# RaspiComm_v3.net
KiCad netlist of a schematic drawn in EAGLE
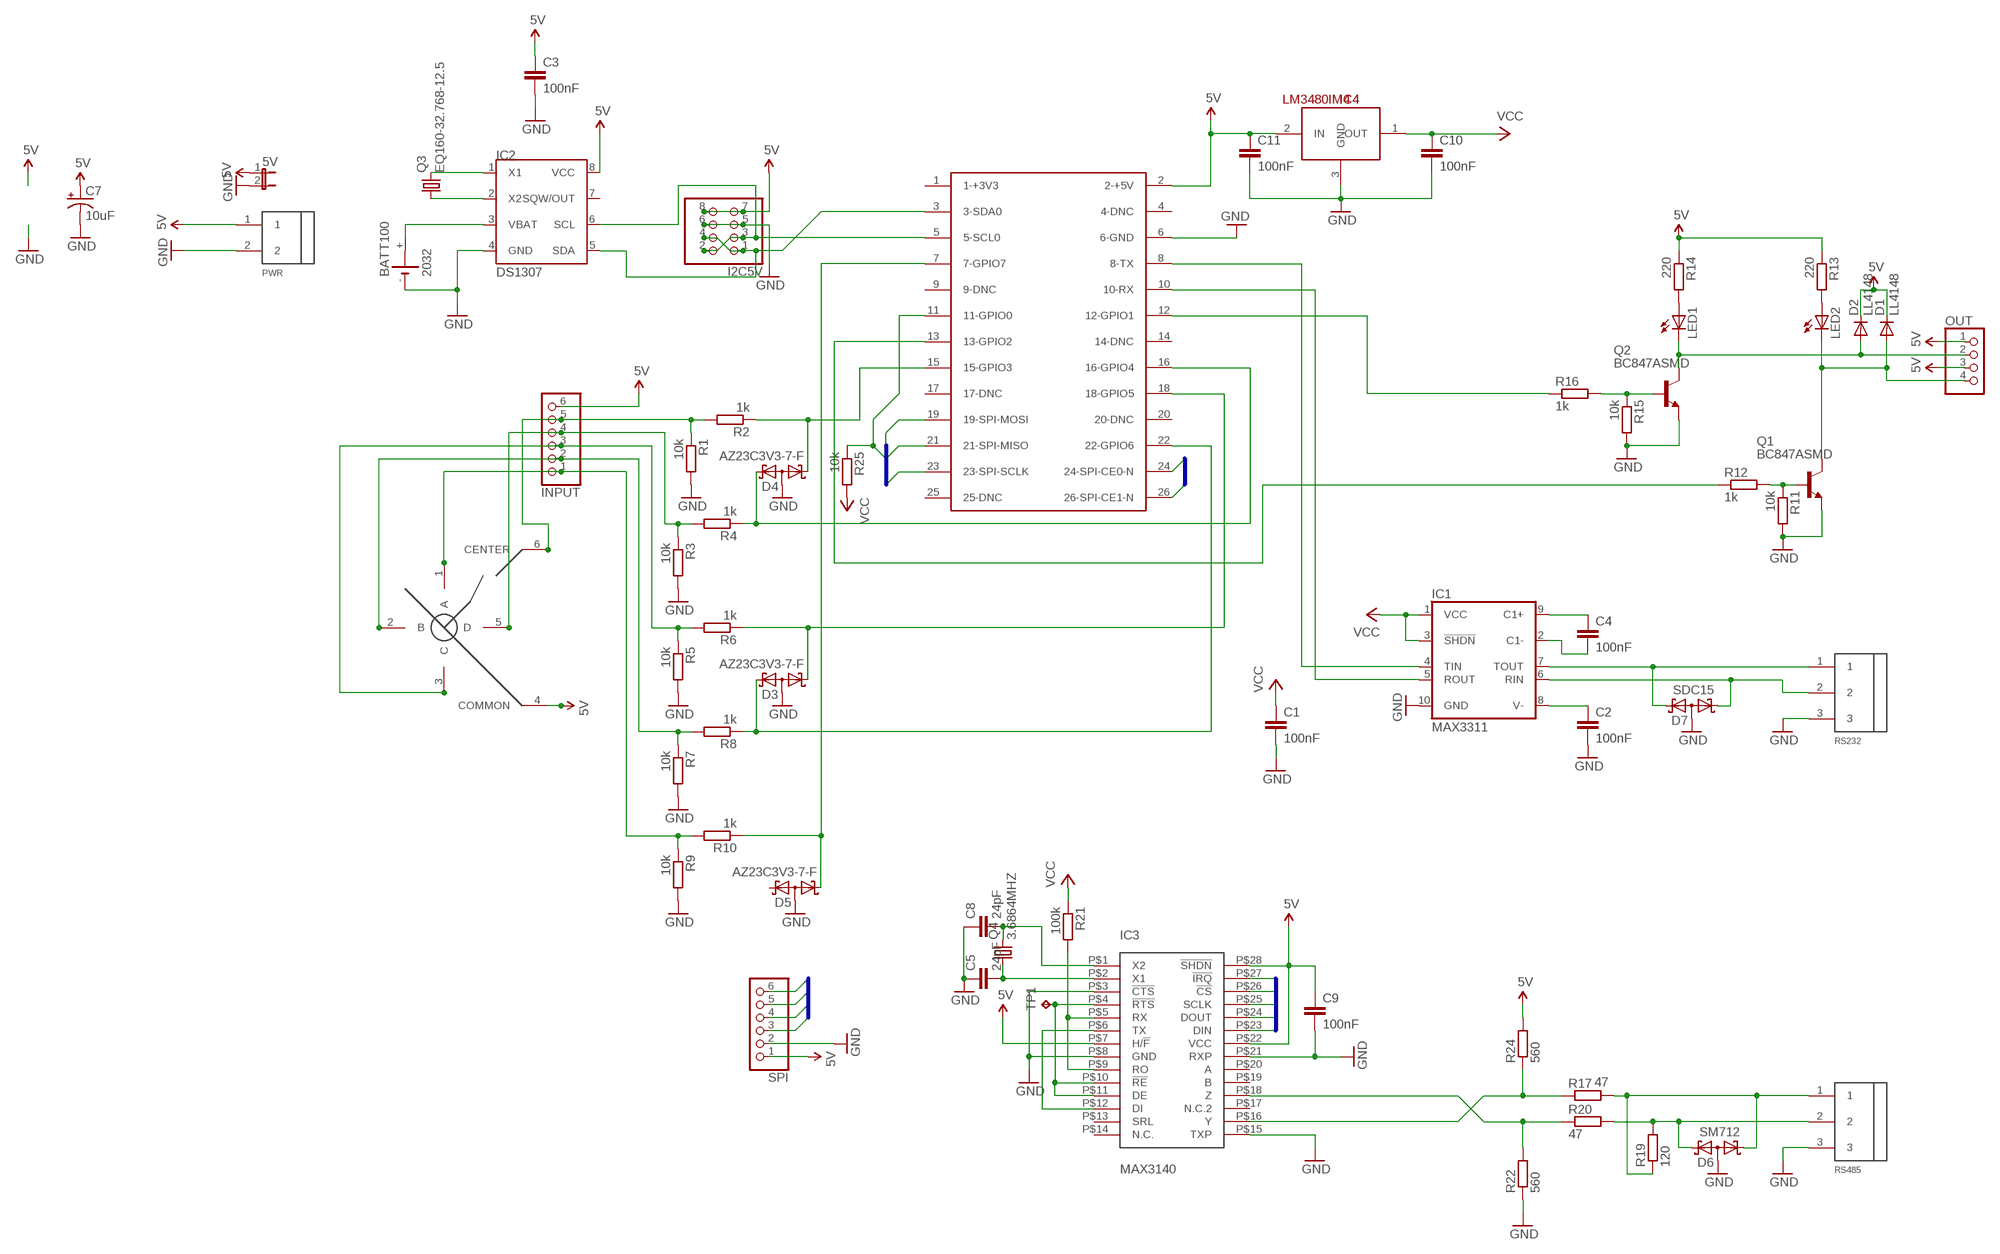
[diagram p0: schematic, sheet 1]

(export (version "E")
  (design (tool "Eeschema 10.0.6"))
  (components
    (comp (ref "5V")
      (value "JP1E")
      (footprint "eagle-import:JP1")
      (libsource (lib "eagle-import") (part "JP1E"))
    )
    (comp (ref "BATT100")
      (value "2032")
      (footprint "eagle-import:KZH20SMD")
      (libsource (lib "eagle-import") (part "2032"))
    )
    (comp (ref "C1")
      (value "100nF")
      (footprint "eagle-import:C0603")
      (libsource (lib "eagle-import") (part "C-EUC0603"))
    )
    (comp (ref "C2")
      (value "100nF")
      (footprint "eagle-import:C0603")
      (libsource (lib "eagle-import") (part "C-EUC0603"))
    )
    (comp (ref "C3")
      (value "100nF")
      (footprint "eagle-import:C0603")
      (libsource (lib "eagle-import") (part "C-EUC0603"))
    )
    (comp (ref "C4")
      (value "100nF")
      (footprint "eagle-import:C0603")
      (libsource (lib "eagle-import") (part "C-EUC0603"))
    )
    (comp (ref "C5")
      (value "24pF")
      (footprint "eagle-import:C0603")
      (libsource (lib "eagle-import") (part "C-EUC0603"))
    )
    (comp (ref "C7")
      (value "10uF")
      (footprint "eagle-import:B(3528-21)")
      (libsource (lib "eagle-import") (part "293DB"))
    )
    (comp (ref "C8")
      (value "24pF")
      (footprint "eagle-import:C0603")
      (libsource (lib "eagle-import") (part "C-EUC0603"))
    )
    (comp (ref "C9")
      (value "100nF")
      (footprint "eagle-import:C0603")
      (libsource (lib "eagle-import") (part "C-EUC0603"))
    )
    (comp (ref "C10")
      (value "100nF")
      (footprint "eagle-import:C0603")
      (libsource (lib "eagle-import") (part "C-EUC0603"))
    )
    (comp (ref "C11")
      (value "100nF")
      (footprint "eagle-import:C0603")
      (libsource (lib "eagle-import") (part "C-EUC0603"))
    )
    (comp (ref "D1")
      (value "LL4148")
      (footprint "eagle-import:SOD80C")
      (libsource (lib "eagle-import") (part "DIODE-SOD80C"))
    )
    (comp (ref "D2")
      (value "LL4148")
      (footprint "eagle-import:SOD80C")
      (libsource (lib "eagle-import") (part "DIODE-SOD80C"))
    )
    (comp (ref "D3")
      (value "AZ23C3V3-7-F")
      (footprint "eagle-import:SOT23")
      (libsource (lib "eagle-import") (part "AZ23CXXX"))
    )
    (comp (ref "D4")
      (value "AZ23C3V3-7-F")
      (footprint "eagle-import:SOT23")
      (libsource (lib "eagle-import") (part "AZ23CXXX"))
    )
    (comp (ref "D5")
      (value "AZ23C3V3-7-F")
      (footprint "eagle-import:SOT23")
      (libsource (lib "eagle-import") (part "AZ23CXXX"))
    )
    (comp (ref "D6")
      (value "SM712")
      (footprint "eagle-import:SOT23")
      (libsource (lib "eagle-import") (part "AZ23CXXX"))
    )
    (comp (ref "D7")
      (value "SDC15")
      (footprint "eagle-import:SOT23")
      (libsource (lib "eagle-import") (part "AZ23CXXX"))
    )
    (comp (ref "I2C5V")
      (value "PINHD-2X4_2.54-SMD")
      (footprint "eagle-import:2X04SMD")
      (libsource (lib "eagle-import") (part "PINHD-2X4_2.54-SMD"))
    )
    (comp (ref "IC1")
      (value "MAX3311")
      (footprint "eagle-import:UMAX10")
      (fields (field (name "MF") "MAXIM") (field (name "MPN") "MAX3311ECUB+"))
      (libsource (lib "eagle-import") (part "MAX3311"))
    )
    (comp (ref "IC2")
      (value "DS1307")
      (footprint "eagle-import:SOIC-8")
      (libsource (lib "eagle-import") (part "DS1307"))
    )
    (comp (ref "IC3")
      (value "MAX3140")
      (footprint "eagle-import:QSOP28")
      (libsource (lib "eagle-import") (part "MAX3140"))
    )
    (comp (ref "IC4")
      (value "LM3480IM4")
      (footprint "eagle-import:SOT23-3")
      (libsource (lib "eagle-import") (part "LM3480IM4"))
    )
    (comp (ref "INPUT")
      (value "PINHD-1X6_2.00")
      (footprint "eagle-import:1X06M")
      (libsource (lib "eagle-import") (part "PINHD-1X6_2.00"))
    )
    (comp (ref "LED1")
      (value "LEDSML0805")
      (footprint "eagle-import:SML0805")
      (libsource (lib "eagle-import") (part "LEDSML0805"))
    )
    (comp (ref "LED2")
      (value "LEDSML0805")
      (footprint "eagle-import:SML0805")
      (libsource (lib "eagle-import") (part "LEDSML0805"))
    )
    (comp (ref "OUT")
      (value "PINHD-1X4_2.00")
      (footprint "eagle-import:1X04M")
      (libsource (lib "eagle-import") (part "PINHD-1X4_2.00"))
    )
    (comp (ref "PWR")
      (value "31182102")
      (footprint "eagle-import:31182102")
      (libsource (lib "eagle-import") (part "31182102"))
    )
    (comp (ref "Q1")
      (value "BC847ASMD")
      (footprint "eagle-import:SOT23")
      (libsource (lib "eagle-import") (part "BC847SMDA"))
    )
    (comp (ref "Q2")
      (value "BC847ASMD")
      (footprint "eagle-import:SOT23")
      (libsource (lib "eagle-import") (part "BC847SMDA"))
    )
    (comp (ref "Q3")
      (value "EQ160-32.768-12.5")
      (footprint "eagle-import:EQ160")
      (libsource (lib "eagle-import") (part "EQ160"))
    )
    (comp (ref "Q4")
      (value "3.6864MHZ")
      (footprint "eagle-import:49USMX")
      (libsource (lib "eagle-import") (part "QUARTZ49USMX"))
    )
    (comp (ref "R1")
      (value "10k")
      (footprint "eagle-import:R0603")
      (libsource (lib "eagle-import") (part "R-EU_R0603"))
    )
    (comp (ref "R2")
      (value "1k")
      (footprint "eagle-import:R0603")
      (libsource (lib "eagle-import") (part "R-EU_R0603"))
    )
    (comp (ref "R3")
      (value "10k")
      (footprint "eagle-import:R0603")
      (libsource (lib "eagle-import") (part "R-EU_R0603"))
    )
    (comp (ref "R4")
      (value "1k")
      (footprint "eagle-import:R0603")
      (libsource (lib "eagle-import") (part "R-EU_R0603"))
    )
    (comp (ref "R5")
      (value "10k")
      (footprint "eagle-import:R0603")
      (libsource (lib "eagle-import") (part "R-EU_R0603"))
    )
    (comp (ref "R6")
      (value "1k")
      (footprint "eagle-import:R0603")
      (libsource (lib "eagle-import") (part "R-EU_R0603"))
    )
    (comp (ref "R7")
      (value "10k")
      (footprint "eagle-import:R0603")
      (libsource (lib "eagle-import") (part "R-EU_R0603"))
    )
    (comp (ref "R8")
      (value "1k")
      (footprint "eagle-import:R0603")
      (libsource (lib "eagle-import") (part "R-EU_R0603"))
    )
    (comp (ref "R9")
      (value "10k")
      (footprint "eagle-import:R0603")
      (libsource (lib "eagle-import") (part "R-EU_R0603"))
    )
    (comp (ref "R10")
      (value "1k")
      (footprint "eagle-import:R0603")
      (libsource (lib "eagle-import") (part "R-EU_R0603"))
    )
    (comp (ref "R11")
      (value "10k")
      (footprint "eagle-import:R0603")
      (libsource (lib "eagle-import") (part "R-EU_R0603"))
    )
    (comp (ref "R12")
      (value "1k")
      (footprint "eagle-import:R0603")
      (libsource (lib "eagle-import") (part "R-EU_R0603"))
    )
    (comp (ref "R13")
      (value "220")
      (footprint "eagle-import:R0603")
      (libsource (lib "eagle-import") (part "R-EU_R0603"))
    )
    (comp (ref "R14")
      (value "220")
      (footprint "eagle-import:R0603")
      (libsource (lib "eagle-import") (part "R-EU_R0603"))
    )
    (comp (ref "R15")
      (value "10k")
      (footprint "eagle-import:R0603")
      (libsource (lib "eagle-import") (part "R-EU_R0603"))
    )
    (comp (ref "R16")
      (value "1k")
      (footprint "eagle-import:R0603")
      (libsource (lib "eagle-import") (part "R-EU_R0603"))
    )
    (comp (ref "R17")
      (value "47")
      (footprint "eagle-import:R1206")
      (libsource (lib "eagle-import") (part "R-EU_R1206"))
    )
    (comp (ref "R19")
      (value "120")
      (footprint "eagle-import:R1206")
      (libsource (lib "eagle-import") (part "R-EU_R1206"))
    )
    (comp (ref "R20")
      (value "47")
      (footprint "eagle-import:R1206")
      (libsource (lib "eagle-import") (part "R-EU_R1206"))
    )
    (comp (ref "R21")
      (value "100k")
      (footprint "eagle-import:R0603")
      (libsource (lib "eagle-import") (part "R-EU_R0603"))
    )
    (comp (ref "R22")
      (value "560")
      (footprint "eagle-import:R0603")
      (libsource (lib "eagle-import") (part "R-EU_R0603"))
    )
    (comp (ref "R24")
      (value "560")
      (footprint "eagle-import:R0603")
      (libsource (lib "eagle-import") (part "R-EU_R0603"))
    )
    (comp (ref "R25")
      (value "10k")
      (footprint "eagle-import:R0603")
      (libsource (lib "eagle-import") (part "R-EU_R0603"))
    )
    (comp (ref "RS232")
      (value "31182103")
      (footprint "eagle-import:31182103")
      (libsource (lib "eagle-import") (part "31182103"))
    )
    (comp (ref "RS485")
      (value "31182103")
      (footprint "eagle-import:31182103")
      (libsource (lib "eagle-import") (part "31182103"))
    )
    (comp (ref "SPI")
      (value "PINHD-1X6_2.00")
      (footprint "eagle-import:1X06M")
      (libsource (lib "eagle-import") (part "PINHD-1X6_2.00"))
    )
    (comp (ref "SW1")
      (value "SKQUDBE010")
      (footprint "eagle-import:SKQU-SMD")
      (libsource (lib "eagle-import") (part "SKQUSMD"))
    )
    (comp (ref "TP1")
      (value "TPB1,27")
      (footprint "eagle-import:B1,27")
      (libsource (lib "eagle-import") (part "TPB1,27"))
    )
    (comp (ref "U$7")
      (value "RASPBERRY-PIHEADER")
      (footprint "eagle-import:RASPI_GPIO_HEADER")
      (libsource (lib "eagle-import") (part "RASPBERRY-PIHEADER"))
    )
  )
  (nets
    (net (code "1") (name "/CS1") (class "Default")
      (node (ref "IC3") (pin "P$26") (pinfunction "~{CS}_P$26") (pintype "bidirectional"))
      (node (ref "U$7") (pin "24") (pinfunction "24-SPI-CE0-N_24") (pintype "bidirectional"))
    )
    (net (code "2") (name "/CS2") (class "Default")
      (node (ref "SPI") (pin "3") (pinfunction "3_3") (pintype "passive"))
      (node (ref "U$7") (pin "26") (pinfunction "26-SPI-CE1-N_26") (pintype "bidirectional"))
    )
    (net (code "3") (name "/IRQ") (class "Default")
      (node (ref "IC3") (pin "P$27") (pinfunction "~{IRQ}_P$27") (pintype "bidirectional"))
      (node (ref "R25") (pin "1") (pinfunction "1_1") (pintype "passive"))
      (node (ref "U$7") (pin "11") (pinfunction "11-GPIO0_11") (pintype "bidirectional"))
    )
    (net (code "4") (name "/MISO") (class "Default")
      (node (ref "IC3") (pin "P$24") (pinfunction "DOUT_P$24") (pintype "bidirectional"))
      (node (ref "SPI") (pin "5") (pinfunction "5_5") (pintype "passive"))
      (node (ref "U$7") (pin "21") (pinfunction "21-SPI-MISO_21") (pintype "bidirectional"))
    )
    (net (code "5") (name "/MOSI") (class "Default")
      (node (ref "IC3") (pin "P$23") (pinfunction "DIN_P$23") (pintype "bidirectional"))
      (node (ref "SPI") (pin "6") (pinfunction "6_6") (pintype "passive"))
      (node (ref "U$7") (pin "19") (pinfunction "19-SPI-MOSI_19") (pintype "bidirectional"))
    )
    (net (code "6") (name "/SCLK") (class "Default")
      (node (ref "IC3") (pin "P$25") (pinfunction "SCLK_P$25") (pintype "bidirectional"))
      (node (ref "SPI") (pin "4") (pinfunction "4_4") (pintype "passive"))
      (node (ref "U$7") (pin "23") (pinfunction "23-SPI-SCLK_23") (pintype "bidirectional"))
    )
    (net (code "7") (name "5V") (class "Default")
      (node (ref "5V") (pin "1") (pinfunction "1_1") (pintype "passive"))
      (node (ref "C11") (pin "1") (pinfunction "1_1") (pintype "passive"))
      (node (ref "C3") (pin "1") (pinfunction "1_1") (pintype "passive"))
      (node (ref "C7") (pin "+") (pinfunction "+_+") (pintype "passive"))
      (node (ref "C9") (pin "1") (pinfunction "1_1") (pintype "passive"))
      (node (ref "D1") (pin "C") (pinfunction "C_C") (pintype "passive"))
      (node (ref "D2") (pin "C") (pinfunction "C_C") (pintype "passive"))
      (node (ref "I2C5V") (pin "7") (pinfunction "7_7") (pintype "passive"))
      (node (ref "I2C5V") (pin "8") (pinfunction "8_8") (pintype "passive"))
      (node (ref "IC2") (pin "8") (pinfunction "VCC_8") (pintype "power_in"))
      (node (ref "IC3") (pin "P$22") (pinfunction "VCC_P$22") (pintype "bidirectional"))
      (node (ref "IC3") (pin "P$28") (pinfunction "~{SHDN}_P$28") (pintype "bidirectional"))
      (node (ref "IC3") (pin "P$7") (pinfunction "H/~{F}_P$7") (pintype "bidirectional"))
      (node (ref "IC4") (pin "2") (pinfunction "IN_2") (pintype "bidirectional"))
      (node (ref "INPUT") (pin "6") (pinfunction "6_6") (pintype "passive"))
      (node (ref "OUT") (pin "1") (pinfunction "1_1") (pintype "passive"))
      (node (ref "OUT") (pin "3") (pinfunction "3_3") (pintype "passive"))
      (node (ref "PWR") (pin "1") (pinfunction "1_1") (pintype "bidirectional"))
      (node (ref "R13") (pin "1") (pinfunction "1_1") (pintype "passive"))
      (node (ref "R14") (pin "1") (pinfunction "1_1") (pintype "passive"))
      (node (ref "R24") (pin "2") (pinfunction "2_2") (pintype "passive"))
      (node (ref "SPI") (pin "1") (pinfunction "1_1") (pintype "passive"))
      (node (ref "SW1") (pin "4") (pinfunction "COMMON_4") (pintype "bidirectional"))
      (node (ref "U$7") (pin "2") (pinfunction "2-+5V_2") (pintype "bidirectional"))
    )
    (net (code "8") (name "GND") (class "Default")
      (node (ref "5V") (pin "2") (pinfunction "2_2") (pintype "passive"))
      (node (ref "BATT100") (pin "-") (pinfunction "-_-") (pintype "passive"))
      (node (ref "C1") (pin "2") (pinfunction "2_2") (pintype "passive"))
      (node (ref "C10") (pin "2") (pinfunction "2_2") (pintype "passive"))
      (node (ref "C11") (pin "2") (pinfunction "2_2") (pintype "passive"))
      (node (ref "C2") (pin "2") (pinfunction "2_2") (pintype "passive"))
      (node (ref "C3") (pin "2") (pinfunction "2_2") (pintype "passive"))
      (node (ref "C5") (pin "1") (pinfunction "1_1") (pintype "passive"))
      (node (ref "C7") (pin "-") (pinfunction "-_-") (pintype "passive"))
      (node (ref "C8") (pin "1") (pinfunction "1_1") (pintype "passive"))
      (node (ref "C9") (pin "2") (pinfunction "2_2") (pintype "passive"))
      (node (ref "D3") (pin "3") (pinfunction "AA_3") (pintype "passive"))
      (node (ref "D4") (pin "3") (pinfunction "AA_3") (pintype "passive"))
      (node (ref "D5") (pin "3") (pinfunction "AA_3") (pintype "passive"))
      (node (ref "D6") (pin "3") (pinfunction "AA_3") (pintype "passive"))
      (node (ref "D7") (pin "3") (pinfunction "AA_3") (pintype "passive"))
      (node (ref "I2C5V") (pin "5") (pinfunction "5_5") (pintype "passive"))
      (node (ref "I2C5V") (pin "6") (pinfunction "6_6") (pintype "passive"))
      (node (ref "IC1") (pin "10") (pinfunction "GND_10") (pintype "power_in"))
      (node (ref "IC2") (pin "4") (pinfunction "GND_4") (pintype "power_in"))
      (node (ref "IC3") (pin "P$15") (pinfunction "TXP_P$15") (pintype "bidirectional"))
      (node (ref "IC3") (pin "P$21") (pinfunction "RXP_P$21") (pintype "bidirectional"))
      (node (ref "IC3") (pin "P$3") (pinfunction "~{CTS}_P$3") (pintype "bidirectional"))
      (node (ref "IC3") (pin "P$8") (pinfunction "GND_P$8") (pintype "bidirectional"))
      (node (ref "IC4") (pin "3") (pinfunction "GND_3") (pintype "bidirectional"))
      (node (ref "PWR") (pin "2") (pinfunction "2_2") (pintype "bidirectional"))
      (node (ref "Q1") (pin "2") (pinfunction "E_2") (pintype "passive"))
      (node (ref "Q2") (pin "2") (pinfunction "E_2") (pintype "passive"))
      (node (ref "R1") (pin "2") (pinfunction "2_2") (pintype "passive"))
      (node (ref "R11") (pin "2") (pinfunction "2_2") (pintype "passive"))
      (node (ref "R15") (pin "2") (pinfunction "2_2") (pintype "passive"))
      (node (ref "R22") (pin "1") (pinfunction "1_1") (pintype "passive"))
      (node (ref "R3") (pin "2") (pinfunction "2_2") (pintype "passive"))
      (node (ref "R5") (pin "2") (pinfunction "2_2") (pintype "passive"))
      (node (ref "R7") (pin "2") (pinfunction "2_2") (pintype "passive"))
      (node (ref "R9") (pin "2") (pinfunction "2_2") (pintype "passive"))
      (node (ref "RS232") (pin "3") (pinfunction "3_3") (pintype "bidirectional"))
      (node (ref "RS485") (pin "3") (pinfunction "3_3") (pintype "bidirectional"))
      (node (ref "SPI") (pin "2") (pinfunction "2_2") (pintype "passive"))
      (node (ref "U$7") (pin "6") (pinfunction "6-GND_6") (pintype "bidirectional"))
    )
    (net (code "9") (name "Net-(D3-K1)") (class "Default")
      (node (ref "D3") (pin "1") (pinfunction "K1_1") (pintype "passive"))
      (node (ref "R6") (pin "1") (pinfunction "1_1") (pintype "passive"))
      (node (ref "U$7") (pin "18") (pinfunction "18-GPIO5_18") (pintype "bidirectional"))
    )
    (net (code "10") (name "Net-(D3-K2)") (class "Default")
      (node (ref "D3") (pin "2") (pinfunction "K2_2") (pintype "passive"))
      (node (ref "R8") (pin "1") (pinfunction "1_1") (pintype "passive"))
      (node (ref "U$7") (pin "22") (pinfunction "22-GPIO6_22") (pintype "bidirectional"))
    )
    (net (code "11") (name "Net-(D4-K1)") (class "Default")
      (node (ref "D4") (pin "1") (pinfunction "K1_1") (pintype "passive"))
      (node (ref "R2") (pin "1") (pinfunction "1_1") (pintype "passive"))
      (node (ref "U$7") (pin "15") (pinfunction "15-GPIO3_15") (pintype "bidirectional"))
    )
    (net (code "12") (name "Net-(D4-K2)") (class "Default")
      (node (ref "D4") (pin "2") (pinfunction "K2_2") (pintype "passive"))
      (node (ref "R4") (pin "1") (pinfunction "1_1") (pintype "passive"))
      (node (ref "U$7") (pin "16") (pinfunction "16-GPIO4_16") (pintype "bidirectional"))
    )
    (net (code "13") (name "Net-(D5-K1)") (class "Default")
      (node (ref "D5") (pin "1") (pinfunction "K1_1") (pintype "passive"))
      (node (ref "R10") (pin "1") (pinfunction "1_1") (pintype "passive"))
      (node (ref "U$7") (pin "7") (pinfunction "7-GPIO7_7") (pintype "bidirectional"))
    )
    (net (code "14") (name "Net-(D6-K1)") (class "Default")
      (node (ref "D6") (pin "1") (pinfunction "K1_1") (pintype "passive"))
      (node (ref "R17") (pin "2") (pinfunction "2_2") (pintype "passive"))
      (node (ref "R19") (pin "1") (pinfunction "1_1") (pintype "passive"))
      (node (ref "RS485") (pin "1") (pinfunction "1_1") (pintype "bidirectional"))
    )
    (net (code "15") (name "Net-(D6-K2)") (class "Default")
      (node (ref "D6") (pin "2") (pinfunction "K2_2") (pintype "passive"))
      (node (ref "R19") (pin "2") (pinfunction "2_2") (pintype "passive"))
      (node (ref "R20") (pin "2") (pinfunction "2_2") (pintype "passive"))
      (node (ref "RS485") (pin "2") (pinfunction "2_2") (pintype "bidirectional"))
    )
    (net (code "16") (name "Net-(D7-K1)") (class "Default")
      (node (ref "D7") (pin "1") (pinfunction "K1_1") (pintype "passive"))
      (node (ref "IC1") (pin "6") (pinfunction "RIN_6") (pintype "input"))
      (node (ref "RS232") (pin "2") (pinfunction "2_2") (pintype "bidirectional"))
    )
    (net (code "17") (name "Net-(D7-K2)") (class "Default")
      (node (ref "D7") (pin "2") (pinfunction "K2_2") (pintype "passive"))
      (node (ref "IC1") (pin "7") (pinfunction "TOUT_7") (pintype "output"))
      (node (ref "RS232") (pin "1") (pinfunction "1_1") (pintype "bidirectional"))
    )
    (net (code "18") (name "Net-(IC1-C1+)") (class "Default")
      (node (ref "C4") (pin "1") (pinfunction "1_1") (pintype "passive"))
      (node (ref "IC1") (pin "9") (pinfunction "C1+_9") (pintype "passive"))
    )
    (net (code "19") (name "Net-(IC1-C1-)") (class "Default")
      (node (ref "C4") (pin "2") (pinfunction "2_2") (pintype "passive"))
      (node (ref "IC1") (pin "2") (pinfunction "C1-_2") (pintype "passive"))
    )
    (net (code "20") (name "Net-(IC1-ROUT)") (class "Default")
      (node (ref "IC1") (pin "5") (pinfunction "ROUT_5") (pintype "output"))
      (node (ref "U$7") (pin "10") (pinfunction "10-RX_10") (pintype "bidirectional"))
    )
    (net (code "21") (name "Net-(IC1-TIN)") (class "Default")
      (node (ref "IC1") (pin "4") (pinfunction "TIN_4") (pintype "input"))
      (node (ref "U$7") (pin "8") (pinfunction "8-TX_8") (pintype "bidirectional"))
    )
    (net (code "22") (name "Net-(IC1-V-)") (class "Default")
      (node (ref "C2") (pin "1") (pinfunction "1_1") (pintype "passive"))
      (node (ref "IC1") (pin "8") (pinfunction "V-_8") (pintype "passive"))
    )
    (net (code "23") (name "Net-(IC2-SCL)") (class "Default")
      (node (ref "I2C5V") (pin "2") (pinfunction "2_2") (pintype "passive"))
      (node (ref "I2C5V") (pin "3") (pinfunction "3_3") (pintype "passive"))
      (node (ref "IC2") (pin "6") (pinfunction "SCL_6") (pintype "input"))
      (node (ref "U$7") (pin "5") (pinfunction "5-SCL0_5") (pintype "bidirectional"))
    )
    (net (code "24") (name "Net-(IC2-SDA)") (class "Default")
      (node (ref "I2C5V") (pin "1") (pinfunction "1_1") (pintype "passive"))
      (node (ref "I2C5V") (pin "4") (pinfunction "4_4") (pintype "passive"))
      (node (ref "IC2") (pin "5") (pinfunction "SDA_5") (pintype "bidirectional"))
      (node (ref "U$7") (pin "3") (pinfunction "3-SDA0_3") (pintype "bidirectional"))
    )
    (net (code "25") (name "Net-(IC2-VBAT)") (class "Default")
      (node (ref "BATT100") (pin "+") (pinfunction "+_+") (pintype "passive"))
      (node (ref "IC2") (pin "3") (pinfunction "VBAT_3") (pintype "power_in"))
    )
    (net (code "26") (name "Net-(IC2-X1)") (class "Default")
      (node (ref "IC2") (pin "1") (pinfunction "X1_1") (pintype "input"))
      (node (ref "Q3") (pin "P$2") (pinfunction "2_P$2") (pintype "passive"))
    )
    (net (code "27") (name "Net-(IC2-X2)") (class "Default")
      (node (ref "IC2") (pin "2") (pinfunction "X2_2") (pintype "output"))
      (node (ref "Q3") (pin "P$1") (pinfunction "1_P$1") (pintype "passive"))
    )
    (net (code "28") (name "Net-(IC3-DE)") (class "Default")
      (node (ref "IC3") (pin "P$10") (pinfunction "~{RE}_P$10") (pintype "bidirectional"))
      (node (ref "IC3") (pin "P$11") (pinfunction "DE_P$11") (pintype "bidirectional"))
      (node (ref "IC3") (pin "P$4") (pinfunction "~{RTS}_P$4") (pintype "bidirectional"))
      (node (ref "TP1") (pin "TP") (pinfunction "TP_TP") (pintype "input"))
    )
    (net (code "29") (name "Net-(IC3-DI)") (class "Default")
      (node (ref "IC3") (pin "P$12") (pinfunction "DI_P$12") (pintype "bidirectional"))
      (node (ref "IC3") (pin "P$6") (pinfunction "TX_P$6") (pintype "bidirectional"))
    )
    (net (code "30") (name "Net-(IC3-RO)") (class "Default")
      (node (ref "IC3") (pin "P$5") (pinfunction "RX_P$5") (pintype "bidirectional"))
      (node (ref "IC3") (pin "P$9") (pinfunction "RO_P$9") (pintype "bidirectional"))
      (node (ref "R21") (pin "2") (pinfunction "2_2") (pintype "passive"))
    )
    (net (code "31") (name "Net-(IC3-X1)") (class "Default")
      (node (ref "C5") (pin "2") (pinfunction "2_2") (pintype "passive"))
      (node (ref "IC3") (pin "P$2") (pinfunction "X1_P$2") (pintype "bidirectional"))
      (node (ref "Q4") (pin "P$1") (pinfunction "1_P$1") (pintype "passive"))
    )
    (net (code "32") (name "Net-(IC3-X2)") (class "Default")
      (node (ref "C8") (pin "2") (pinfunction "2_2") (pintype "passive"))
      (node (ref "IC3") (pin "P$1") (pinfunction "X2_P$1") (pintype "bidirectional"))
      (node (ref "Q4") (pin "P$2") (pinfunction "2_P$2") (pintype "passive"))
    )
    (net (code "33") (name "Net-(IC3-Y)") (class "Default")
      (node (ref "IC3") (pin "P$16") (pinfunction "Y_P$16") (pintype "bidirectional"))
      (node (ref "R17") (pin "1") (pinfunction "1_1") (pintype "passive"))
      (node (ref "R24") (pin "1") (pinfunction "1_1") (pintype "passive"))
    )
    (net (code "34") (name "Net-(IC3-Z)") (class "Default")
      (node (ref "IC3") (pin "P$18") (pinfunction "Z_P$18") (pintype "bidirectional"))
      (node (ref "R20") (pin "1") (pinfunction "1_1") (pintype "passive"))
      (node (ref "R22") (pin "2") (pinfunction "2_2") (pintype "passive"))
    )
    (net (code "35") (name "Net-(LED1-PadA)") (class "Default")
      (node (ref "LED1") (pin "A") (pinfunction "A_A") (pintype "passive"))
      (node (ref "R14") (pin "2") (pinfunction "2_2") (pintype "passive"))
    )
    (net (code "36") (name "Net-(LED2-PadA)") (class "Default")
      (node (ref "LED2") (pin "A") (pinfunction "A_A") (pintype "passive"))
      (node (ref "R13") (pin "2") (pinfunction "2_2") (pintype "passive"))
    )
    (net (code "37") (name "Net-(Q1-B)") (class "Default")
      (node (ref "Q1") (pin "1") (pinfunction "B_1") (pintype "passive"))
      (node (ref "R11") (pin "1") (pinfunction "1_1") (pintype "passive"))
      (node (ref "R12") (pin "2") (pinfunction "2_2") (pintype "passive"))
    )
    (net (code "38") (name "Net-(Q1-C)") (class "Default")
      (node (ref "D1") (pin "A") (pinfunction "A_A") (pintype "passive"))
      (node (ref "LED2") (pin "C") (pinfunction "C_C") (pintype "passive"))
      (node (ref "OUT") (pin "4") (pinfunction "4_4") (pintype "passive"))
      (node (ref "Q1") (pin "3") (pinfunction "C_3") (pintype "passive"))
    )
    (net (code "39") (name "Net-(Q2-B)") (class "Default")
      (node (ref "Q2") (pin "1") (pinfunction "B_1") (pintype "passive"))
      (node (ref "R15") (pin "1") (pinfunction "1_1") (pintype "passive"))
      (node (ref "R16") (pin "2") (pinfunction "2_2") (pintype "passive"))
    )
    (net (code "40") (name "Net-(Q2-C)") (class "Default")
      (node (ref "D2") (pin "A") (pinfunction "A_A") (pintype "passive"))
      (node (ref "LED1") (pin "C") (pinfunction "C_C") (pintype "passive"))
      (node (ref "OUT") (pin "2") (pinfunction "2_2") (pintype "passive"))
      (node (ref "Q2") (pin "3") (pinfunction "C_3") (pintype "passive"))
    )
    (net (code "41") (name "Net-(SW1-A)") (class "Default")
      (node (ref "INPUT") (pin "1") (pinfunction "1_1") (pintype "passive"))
      (node (ref "R10") (pin "2") (pinfunction "2_2") (pintype "passive"))
      (node (ref "R9") (pin "1") (pinfunction "1_1") (pintype "passive"))
      (node (ref "SW1") (pin "1") (pinfunction "A_1") (pintype "bidirectional"))
    )
    (net (code "42") (name "Net-(SW1-B)") (class "Default")
      (node (ref "INPUT") (pin "2") (pinfunction "2_2") (pintype "passive"))
      (node (ref "R7") (pin "1") (pinfunction "1_1") (pintype "passive"))
      (node (ref "R8") (pin "2") (pinfunction "2_2") (pintype "passive"))
      (node (ref "SW1") (pin "2") (pinfunction "B_2") (pintype "bidirectional"))
    )
    (net (code "43") (name "Net-(SW1-C)") (class "Default")
      (node (ref "INPUT") (pin "3") (pinfunction "3_3") (pintype "passive"))
      (node (ref "R5") (pin "1") (pinfunction "1_1") (pintype "passive"))
      (node (ref "R6") (pin "2") (pinfunction "2_2") (pintype "passive"))
      (node (ref "SW1") (pin "3") (pinfunction "C_3") (pintype "bidirectional"))
    )
    (net (code "44") (name "Net-(SW1-CENTER)") (class "Default")
      (node (ref "INPUT") (pin "5") (pinfunction "5_5") (pintype "passive"))
      (node (ref "R1") (pin "1") (pinfunction "1_1") (pintype "passive"))
      (node (ref "R2") (pin "2") (pinfunction "2_2") (pintype "passive"))
      (node (ref "SW1") (pin "6") (pinfunction "CENTER_6") (pintype "bidirectional"))
    )
    (net (code "45") (name "Net-(SW1-D)") (class "Default")
      (node (ref "INPUT") (pin "4") (pinfunction "4_4") (pintype "passive"))
      (node (ref "R3") (pin "1") (pinfunction "1_1") (pintype "passive"))
      (node (ref "R4") (pin "2") (pinfunction "2_2") (pintype "passive"))
      (node (ref "SW1") (pin "5") (pinfunction "D_5") (pintype "bidirectional"))
    )
    (net (code "46") (name "Net-(U$7-12-GPIO1)") (class "Default")
      (node (ref "R16") (pin "1") (pinfunction "1_1") (pintype "passive"))
      (node (ref "U$7") (pin "12") (pinfunction "12-GPIO1_12") (pintype "bidirectional"))
    )
    (net (code "47") (name "Net-(U$7-13-GPIO2)") (class "Default")
      (node (ref "R12") (pin "1") (pinfunction "1_1") (pintype "passive"))
      (node (ref "U$7") (pin "13") (pinfunction "13-GPIO2_13") (pintype "bidirectional"))
    )
    (net (code "48") (name "VCC") (class "Default")
      (node (ref "C1") (pin "1") (pinfunction "1_1") (pintype "passive"))
      (node (ref "C10") (pin "1") (pinfunction "1_1") (pintype "passive"))
      (node (ref "IC1") (pin "1") (pinfunction "VCC_1") (pintype "power_in"))
      (node (ref "IC1") (pin "3") (pinfunction "~{SHDN}_3") (pintype "input"))
      (node (ref "IC4") (pin "1") (pinfunction "OUT_1") (pintype "bidirectional"))
      (node (ref "R21") (pin "1") (pinfunction "1_1") (pintype "passive"))
      (node (ref "R25") (pin "2") (pinfunction "2_2") (pintype "passive"))
    )
    (net (code "49") (name "unconnected-(D5-K2-Pad2)") (class "Default")
      (node (ref "D5") (pin "2") (pinfunction "K2_2") (pintype "passive"))
    )
    (net (code "50") (name "unconnected-(IC2-SQW{slash}OUT-Pad7)") (class "Default")
      (node (ref "IC2") (pin "7") (pinfunction "SQW/OUT_7") (pintype "output"))
    )
    (net (code "51") (name "unconnected-(IC3-A-PadP$20)") (class "Default")
      (node (ref "IC3") (pin "P$20") (pinfunction "A_P$20") (pintype "bidirectional"))
    )
    (net (code "52") (name "unconnected-(IC3-B-PadP$19)") (class "Default")
      (node (ref "IC3") (pin "P$19") (pinfunction "B_P$19") (pintype "bidirectional"))
    )
    (net (code "53") (name "unconnected-(IC3-N.C.-PadP$14)") (class "Default")
      (node (ref "IC3") (pin "P$14") (pinfunction "N.C._P$14") (pintype "bidirectional"))
    )
    (net (code "54") (name "unconnected-(IC3-N.C.2-PadP$17)") (class "Default")
      (node (ref "IC3") (pin "P$17") (pinfunction "N.C.2_P$17") (pintype "bidirectional"))
    )
    (net (code "55") (name "unconnected-(IC3-SRL-PadP$13)") (class "Default")
      (node (ref "IC3") (pin "P$13") (pinfunction "SRL_P$13") (pintype "bidirectional"))
    )
    (net (code "56") (name "unconnected-(U$7-1-+3V3-Pad1)") (class "Default")
      (node (ref "U$7") (pin "1") (pinfunction "1-+3V3_1") (pintype "bidirectional"))
    )
    (net (code "57") (name "unconnected-(U$7-4-DNC-Pad4)") (class "Default")
      (node (ref "U$7") (pin "4") (pinfunction "4-DNC_4") (pintype "bidirectional"))
    )
    (net (code "58") (name "unconnected-(U$7-9-DNC-Pad9)") (class "Default")
      (node (ref "U$7") (pin "9") (pinfunction "9-DNC_9") (pintype "bidirectional"))
    )
    (net (code "59") (name "unconnected-(U$7-14-DNC-Pad14)") (class "Default")
      (node (ref "U$7") (pin "14") (pinfunction "14-DNC_14") (pintype "bidirectional"))
    )
    (net (code "60") (name "unconnected-(U$7-17-DNC-Pad17)") (class "Default")
      (node (ref "U$7") (pin "17") (pinfunction "17-DNC_17") (pintype "bidirectional"))
    )
    (net (code "61") (name "unconnected-(U$7-20-DNC-Pad20)") (class "Default")
      (node (ref "U$7") (pin "20") (pinfunction "20-DNC_20") (pintype "bidirectional"))
    )
    (net (code "62") (name "unconnected-(U$7-25-DNC-Pad25)") (class "Default")
      (node (ref "U$7") (pin "25") (pinfunction "25-DNC_25") (pintype "bidirectional"))
    )
  )
)
